# NB-IOT.net
KiCad netlist of a schematic drawn in Altium Designer
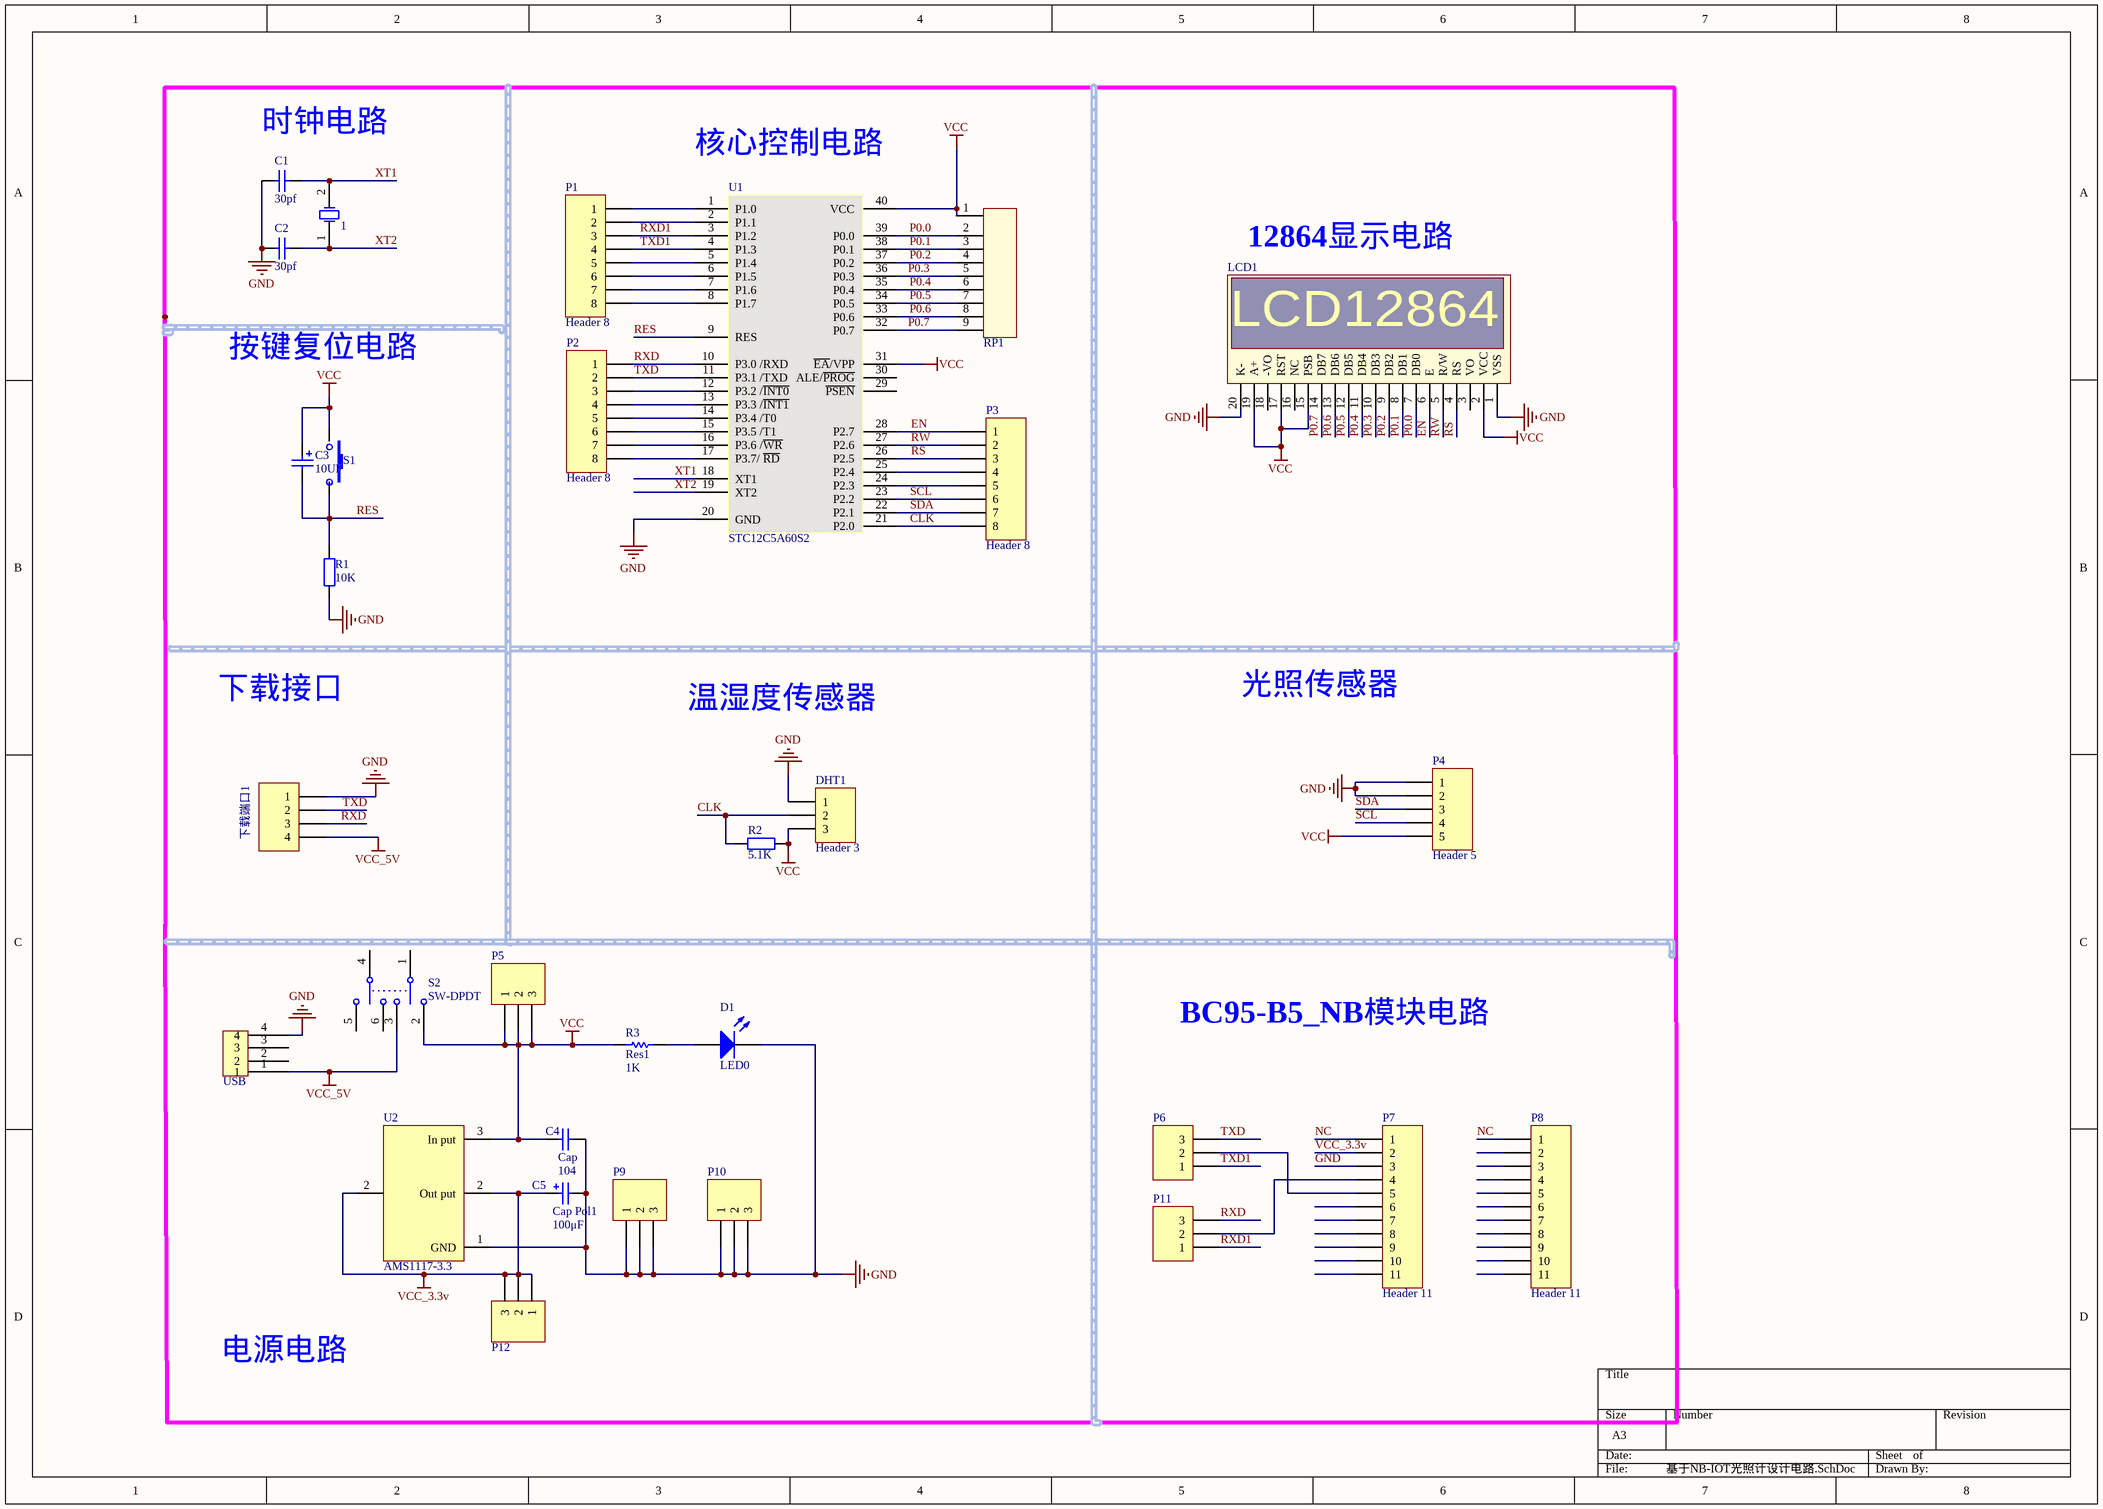
[diagram p0: 基于NB-IOT光照计设计电路.SchDoc]

(export (version "E")
  (design (tool "Eeschema 10.0.6"))
  (components
    (comp (ref "1") (value "XTAL") (footprint "4.直插晶振") (libsource (lib "小莫自创原理图库") (part "XTAL")))
    (comp (ref "C1") (value "30pf") (footprint "2.瓷片电容") (libsource (lib "小莫自创原理图库") (part "CAP")))
    (comp (ref "C2") (value "30pf") (footprint "2.瓷片电容") (libsource (lib "小莫自创原理图库") (part "CAP")))
    (comp (ref "C3") (value "10UF") (footprint "C100A") (libsource (lib "智能环境监测") (part "C-100")))
    (comp (ref "C4")
      (value "Cap")
      (footprint "CAP")
      (description "Capacitor")
      (fields (field (name "ALTIUM_VALUE") "104") (field (name "PUBLISHER") "Altium Limited"))
      (libsource (lib "Student Power Supply") (part "Cap"))
    )
    (comp (ref "C5")
      (value "Cap Pol1")
      (footprint "Cap+")
      (description "Polarized Capacitor (Radial)")
      (fields (field (name "ALTIUM_VALUE") "100μF") (field (name "PUBLISHER") "Altium Limited"))
      (libsource (lib "学生电源") (part "Cap Pol1"))
    )
    (comp (ref "D1")
      (value "LED0")
      (footprint "LED-2")
      (description "Typical INFRARED GaAs LED")
      (fields (field (name "PUBLISHER") "Altium Limited"))
      (libsource (lib "学生电源") (part "LED0"))
    )
    (comp (ref "DHT1")
      (value "Header 3")
      (footprint "HDR1X3")
      (description "Header, 3-Pin")
      (fields (field (name "PUBLISHER") "Altium Limited"))
      (libsource (lib "Miscellaneous Connectors") (part "Header 3"))
    )
    (comp (ref "LCD1") (value "~") (footprint "LCD12864") (libsource (lib "小莫自创原理图库") (part "LCD1")))
    (comp (ref "P1")
      (value "Header 8")
      (footprint "HDR1X8")
      (description "Header, 8-Pin")
      (fields (field (name "PUBLISHER") "Altium Limited"))
      (libsource (lib "Miscellaneous Connectors") (part "Header 8"))
    )
    (comp (ref "P2")
      (value "Header 8")
      (footprint "HDR1X8")
      (description "Header, 8-Pin")
      (fields (field (name "PUBLISHER") "Altium Limited"))
      (libsource (lib "Miscellaneous Connectors") (part "Header 8"))
    )
    (comp (ref "P3")
      (value "Header 8")
      (footprint "HDR1X8")
      (description "Header, 8-Pin")
      (fields (field (name "PUBLISHER") "Altium Limited"))
      (libsource (lib "") (part "Header 8_1"))
    )
    (comp (ref "P4")
      (value "Header 5")
      (footprint "HDR1X5")
      (description "Header, 5-Pin")
      (fields (field (name "PUBLISHER") "Altium Limited"))
      (libsource (lib "Miscellaneous Connectors") (part "Header 5"))
    )
    (comp (ref "P5")
      (value "~")
      (footprint "HDR1X3")
      (description "Header, 3-Pin")
      (fields (field (name "PUBLISHER") "Altium Limited"))
      (libsource (lib "学生电源") (part "Header 3"))
    )
    (comp (ref "P6")
      (value "~")
      (footprint "HDR1X3")
      (description "Header, 3-Pin")
      (fields (field (name "PUBLISHER") "Altium Limited"))
      (libsource (lib "") (part "Header 3_1"))
    )
    (comp (ref "P7")
      (value "Header 11")
      (footprint "HDR1X11")
      (description "Header, 11-Pin")
      (fields (field (name "PUBLISHER") "Altium Limited"))
      (libsource (lib "Miscellaneous Connectors") (part "Header 11"))
    )
    (comp (ref "P8")
      (value "Header 11")
      (footprint "HDR1X11")
      (description "Header, 11-Pin")
      (fields (field (name "PUBLISHER") "Altium Limited"))
      (libsource (lib "Miscellaneous Connectors") (part "Header 11"))
    )
    (comp (ref "P9")
      (value "~")
      (footprint "HDR1X3")
      (description "Header, 3-Pin")
      (fields (field (name "PUBLISHER") "Altium Limited"))
      (libsource (lib "学生电源") (part "Header 3"))
    )
    (comp (ref "P10")
      (value "~")
      (footprint "HDR1X3")
      (description "Header, 3-Pin")
      (fields (field (name "PUBLISHER") "Altium Limited"))
      (libsource (lib "学生电源") (part "Header 3"))
    )
    (comp (ref "P11")
      (value "~")
      (footprint "HDR1X3")
      (description "Header, 3-Pin")
      (fields (field (name "PUBLISHER") "Altium Limited"))
      (libsource (lib "") (part "Header 3_1"))
    )
    (comp (ref "P12")
      (value "~")
      (footprint "HDR1X3")
      (description "Header, 3-Pin")
      (fields (field (name "PUBLISHER") "Altium Limited"))
      (libsource (lib "") (part "Header 3_2"))
    )
    (comp (ref "R1") (value "10K") (footprint "R-300 1/4W") (libsource (lib "小莫自创原理图库") (part "R1")))
    (comp (ref "R2") (value "5.1K") (footprint "R-300 1/4W") (libsource (lib "") (part "R1_1")))
    (comp (ref "R3")
      (value "Res1")
      (footprint "AXIAL-0.3")
      (description "Resistor")
      (fields (field (name "ALTIUM_VALUE") "1K") (field (name "PUBLISHER") "Altium Limited"))
      (libsource (lib "学生电源") (part "Res1"))
    )
    (comp (ref "RP1") (value "RESPACK-8") (footprint "3.排阻") (libsource (lib "小莫自创原理图库") (part "RESPACK-8")))
    (comp (ref "S1")
      (value "~")
      (footprint "KEY1")
      (libsource (lib "altium-import") (part "root_3__烟雾报警.SCHLIB"))
    )
    (comp (ref "S2")
      (value "SW-DPDT")
      (footprint "swichX6")
      (description "Double-Pole, Double-Throw Switch")
      (fields (field (name "PUBLISHER") "Altium Limited"))
      (libsource (lib "Student Power Supply") (part "SW-DPDT"))
    )
    (comp (ref "U1")
      (value "STC12C5A60S2")
      (footprint "DIP-40")
      (libsource (lib "小莫自创原理图库") (part "STC89C52"))
    )
    (comp (ref "U2")
      (value "AMS1117-3.3")
      (footprint "AMS1117")
      (libsource (lib "学生电源") (part "AMS1117-3.3"))
    )
    (comp (ref "Usb1") (value "USB") (footprint "USB-A") (libsource (lib "学生电源") (part "USB")))
    (comp (ref "下载端口1")
      (value "气体")
      (footprint "HDR1X4")
      (description "Header, 4-Pin")
      (fields (field (name "PUBLISHER") "Altium Limited"))
      (libsource (lib "Miscellaneous Connectors") (part "Header 4"))
    )
  )
  (nets
    (net (code "1") (name "/CLK") (class "Default")
      (node (ref "DHT1") (pin "2") (pinfunction "2_2") (pintype "passive"))
      (node (ref "P3") (pin "8") (pinfunction "8_8") (pintype "passive"))
      (node (ref "R2") (pin "2") (pinfunction "2_2") (pintype "passive"))
      (node (ref "U1") (pin "21") (pinfunction "P2.0_21") (pintype "passive"))
    )
    (net (code "2") (name "/EN") (class "Default")
      (node (ref "LCD1") (pin "6") (pinfunction "E_6") (pintype "passive"))
      (node (ref "P3") (pin "1") (pinfunction "1_1") (pintype "passive"))
      (node (ref "U1") (pin "28") (pinfunction "P2.7_28") (pintype "passive"))
    )
    (net (code "3") (name "/NC") (class "Default")
      (node (ref "P7") (pin "1") (pinfunction "1_1") (pintype "passive"))
      (node (ref "P8") (pin "1") (pinfunction "1_1") (pintype "passive"))
    )
    (net (code "4") (name "/P0.0") (class "Default")
      (node (ref "LCD1") (pin "7") (pinfunction "DB0_7") (pintype "passive"))
      (node (ref "RP1") (pin "2") (pinfunction "2_2") (pintype "passive"))
      (node (ref "U1") (pin "39") (pinfunction "P0.0_39") (pintype "passive"))
    )
    (net (code "5") (name "/P0.1") (class "Default")
      (node (ref "LCD1") (pin "8") (pinfunction "DB1_8") (pintype "passive"))
      (node (ref "RP1") (pin "3") (pinfunction "3_3") (pintype "passive"))
      (node (ref "U1") (pin "38") (pinfunction "P0.1_38") (pintype "passive"))
    )
    (net (code "6") (name "/P0.2") (class "Default")
      (node (ref "LCD1") (pin "9") (pinfunction "DB2_9") (pintype "passive"))
      (node (ref "RP1") (pin "4") (pinfunction "4_4") (pintype "passive"))
      (node (ref "U1") (pin "37") (pinfunction "P0.2_37") (pintype "passive"))
    )
    (net (code "7") (name "/P0.3") (class "Default")
      (node (ref "LCD1") (pin "10") (pinfunction "DB3_10") (pintype "passive"))
      (node (ref "RP1") (pin "5") (pinfunction "5_5") (pintype "passive"))
      (node (ref "U1") (pin "36") (pinfunction "P0.3_36") (pintype "passive"))
    )
    (net (code "8") (name "/P0.4") (class "Default")
      (node (ref "LCD1") (pin "11") (pinfunction "DB4_11") (pintype "passive"))
      (node (ref "RP1") (pin "6") (pinfunction "6_6") (pintype "passive"))
      (node (ref "U1") (pin "35") (pinfunction "P0.4_35") (pintype "passive"))
    )
    (net (code "9") (name "/P0.5") (class "Default")
      (node (ref "LCD1") (pin "12") (pinfunction "DB5_12") (pintype "passive"))
      (node (ref "RP1") (pin "7") (pinfunction "7_7") (pintype "passive"))
      (node (ref "U1") (pin "34") (pinfunction "P0.5_34") (pintype "passive"))
    )
    (net (code "10") (name "/P0.6") (class "Default")
      (node (ref "LCD1") (pin "13") (pinfunction "DB6_13") (pintype "passive"))
      (node (ref "RP1") (pin "8") (pinfunction "8_8") (pintype "passive"))
      (node (ref "U1") (pin "33") (pinfunction "P0.6_33") (pintype "passive"))
    )
    (net (code "11") (name "/P0.7") (class "Default")
      (node (ref "LCD1") (pin "14") (pinfunction "DB7_14") (pintype "passive"))
      (node (ref "RP1") (pin "9") (pinfunction "9_9") (pintype "passive"))
      (node (ref "U1") (pin "32") (pinfunction "P0.7_32") (pintype "passive"))
    )
    (net (code "12") (name "/RES") (class "Default")
      (node (ref "C3") (pin "2") (pinfunction "2_2") (pintype "passive"))
      (node (ref "R1") (pin "1") (pinfunction "1_1") (pintype "passive"))
      (node (ref "S1") (pin "2") (pinfunction "2_2") (pintype "passive"))
      (node (ref "U1") (pin "9") (pinfunction "RES_9") (pintype "passive"))
    )
    (net (code "13") (name "/RS") (class "Default")
      (node (ref "LCD1") (pin "4") (pinfunction "RS_4") (pintype "passive"))
      (node (ref "P3") (pin "3") (pinfunction "3_3") (pintype "passive"))
      (node (ref "U1") (pin "26") (pinfunction "P2.5_26") (pintype "passive"))
    )
    (net (code "14") (name "/RW") (class "Default")
      (node (ref "LCD1") (pin "5") (pinfunction "R/W_5") (pintype "passive"))
      (node (ref "P3") (pin "2") (pinfunction "2_2") (pintype "passive"))
      (node (ref "U1") (pin "27") (pinfunction "P2.6_27") (pintype "passive"))
    )
    (net (code "15") (name "/RXD") (class "Default")
      (node (ref "P11") (pin "3") (pinfunction "3_3") (pintype "passive"))
      (node (ref "P2") (pin "1") (pinfunction "1_1") (pintype "passive"))
      (node (ref "U1") (pin "10") (pinfunction "P3.0_/RXD_10") (pintype "passive"))
      (node (ref "下载端口1") (pin "3") (pinfunction "3_3") (pintype "passive"))
    )
    (net (code "16") (name "/RXD1") (class "Default")
      (node (ref "P1") (pin "3") (pinfunction "3_3") (pintype "passive"))
      (node (ref "P11") (pin "1") (pinfunction "1_1") (pintype "passive"))
      (node (ref "U1") (pin "3") (pinfunction "P1.2_3") (pintype "passive"))
    )
    (net (code "17") (name "/SCL") (class "Default")
      (node (ref "P3") (pin "6") (pinfunction "6_6") (pintype "passive"))
      (node (ref "P4") (pin "4") (pinfunction "4_4") (pintype "passive"))
      (node (ref "U1") (pin "23") (pinfunction "P2.2_23") (pintype "passive"))
    )
    (net (code "18") (name "/SDA") (class "Default")
      (node (ref "P3") (pin "7") (pinfunction "7_7") (pintype "passive"))
      (node (ref "P4") (pin "3") (pinfunction "3_3") (pintype "passive"))
      (node (ref "U1") (pin "22") (pinfunction "P2.1_22") (pintype "passive"))
    )
    (net (code "19") (name "/TXD") (class "Default")
      (node (ref "P2") (pin "2") (pinfunction "2_2") (pintype "passive"))
      (node (ref "P6") (pin "3") (pinfunction "3_3") (pintype "passive"))
      (node (ref "U1") (pin "11") (pinfunction "P3.1_/TXD_11") (pintype "passive"))
      (node (ref "下载端口1") (pin "2") (pinfunction "2_2") (pintype "passive"))
    )
    (net (code "20") (name "/TXD1") (class "Default")
      (node (ref "P1") (pin "4") (pinfunction "4_4") (pintype "passive"))
      (node (ref "P6") (pin "1") (pinfunction "1_1") (pintype "passive"))
      (node (ref "U1") (pin "4") (pinfunction "P1.3_4") (pintype "passive"))
    )
    (net (code "21") (name "/XT1") (class "Default")
      (node (ref "1") (pin "2") (pinfunction "OSC2_2") (pintype "passive"))
      (node (ref "C1") (pin "2") (pinfunction "2_2") (pintype "passive"))
      (node (ref "U1") (pin "18") (pinfunction "XT1_18") (pintype "passive"))
    )
    (net (code "22") (name "/XT2") (class "Default")
      (node (ref "1") (pin "1") (pinfunction "OSC1_1") (pintype "passive"))
      (node (ref "C2") (pin "2") (pinfunction "2_2") (pintype "passive"))
      (node (ref "U1") (pin "19") (pinfunction "XT2_19") (pintype "passive"))
    )
    (net (code "23") (name "GND") (class "Default")
      (node (ref "C1") (pin "1") (pinfunction "1_1") (pintype "passive"))
      (node (ref "C2") (pin "1") (pinfunction "1_1") (pintype "passive"))
      (node (ref "C4") (pin "2") (pinfunction "2_2") (pintype "passive"))
      (node (ref "C5") (pin "2") (pinfunction "2_2") (pintype "passive"))
      (node (ref "D1") (pin "2") (pinfunction "K_2") (pintype "passive"))
      (node (ref "DHT1") (pin "1") (pinfunction "1_1") (pintype "passive"))
      (node (ref "LCD1") (pin "1") (pinfunction "VSS_1") (pintype "passive"))
      (node (ref "LCD1") (pin "20") (pinfunction "K-_20") (pintype "passive"))
      (node (ref "P10") (pin "1") (pinfunction "1_1") (pintype "passive"))
      (node (ref "P10") (pin "2") (pinfunction "2_2") (pintype "passive"))
      (node (ref "P10") (pin "3") (pinfunction "3_3") (pintype "passive"))
      (node (ref "P4") (pin "1") (pinfunction "1_1") (pintype "passive"))
      (node (ref "P4") (pin "2") (pinfunction "2_2") (pintype "passive"))
      (node (ref "P7") (pin "3") (pinfunction "3_3") (pintype "passive"))
      (node (ref "P9") (pin "1") (pinfunction "1_1") (pintype "passive"))
      (node (ref "P9") (pin "2") (pinfunction "2_2") (pintype "passive"))
      (node (ref "P9") (pin "3") (pinfunction "3_3") (pintype "passive"))
      (node (ref "R1") (pin "2") (pinfunction "2_2") (pintype "passive"))
      (node (ref "U1") (pin "20") (pinfunction "GND_20") (pintype "passive"))
      (node (ref "U2") (pin "1") (pinfunction "GND_1") (pintype "passive"))
      (node (ref "Usb1") (pin "4") (pinfunction "4_4") (pintype "passive"))
      (node (ref "下载端口1") (pin "1") (pinfunction "1_1") (pintype "passive"))
    )
    (net (code "24") (name "Net-(D1-A)") (class "Default")
      (node (ref "D1") (pin "1") (pinfunction "A_1") (pintype "passive"))
      (node (ref "R3") (pin "2") (pinfunction "2_2") (pintype "passive"))
    )
    (net (code "25") (name "Net-(P6-Pad2)") (class "Default")
      (node (ref "P6") (pin "2") (pinfunction "2_2") (pintype "passive"))
      (node (ref "P7") (pin "5") (pinfunction "5_5") (pintype "passive"))
    )
    (net (code "26") (name "Net-(P11-Pad2)") (class "Default")
      (node (ref "P11") (pin "2") (pinfunction "2_2") (pintype "passive"))
      (node (ref "P7") (pin "4") (pinfunction "4_4") (pintype "passive"))
    )
    (net (code "27") (name "Net-(U1-P1.0)") (class "Default")
      (node (ref "P1") (pin "1") (pinfunction "1_1") (pintype "passive"))
      (node (ref "U1") (pin "1") (pinfunction "P1.0_1") (pintype "passive"))
    )
    (net (code "28") (name "Net-(U1-P1.1)") (class "Default")
      (node (ref "P1") (pin "2") (pinfunction "2_2") (pintype "passive"))
      (node (ref "U1") (pin "2") (pinfunction "P1.1_2") (pintype "passive"))
    )
    (net (code "29") (name "Net-(U1-P1.4)") (class "Default")
      (node (ref "P1") (pin "5") (pinfunction "5_5") (pintype "passive"))
      (node (ref "U1") (pin "5") (pinfunction "P1.4_5") (pintype "passive"))
    )
    (net (code "30") (name "Net-(U1-P1.5)") (class "Default")
      (node (ref "P1") (pin "6") (pinfunction "6_6") (pintype "passive"))
      (node (ref "U1") (pin "6") (pinfunction "P1.5_6") (pintype "passive"))
    )
    (net (code "31") (name "Net-(U1-P1.6)") (class "Default")
      (node (ref "P1") (pin "7") (pinfunction "7_7") (pintype "passive"))
      (node (ref "U1") (pin "7") (pinfunction "P1.6_7") (pintype "passive"))
    )
    (net (code "32") (name "Net-(U1-P1.7)") (class "Default")
      (node (ref "P1") (pin "8") (pinfunction "8_8") (pintype "passive"))
      (node (ref "U1") (pin "8") (pinfunction "P1.7_8") (pintype "passive"))
    )
    (net (code "33") (name "Net-(U1-P2.3)") (class "Default")
      (node (ref "P3") (pin "5") (pinfunction "5_5") (pintype "passive"))
      (node (ref "U1") (pin "24") (pinfunction "P2.3_24") (pintype "passive"))
    )
    (net (code "34") (name "Net-(U1-P2.4)") (class "Default")
      (node (ref "P3") (pin "4") (pinfunction "4_4") (pintype "passive"))
      (node (ref "U1") (pin "25") (pinfunction "P2.4_25") (pintype "passive"))
    )
    (net (code "35") (name "Net-(U1-P3.2_{slash}~{INT0})") (class "Default")
      (node (ref "P2") (pin "3") (pinfunction "3_3") (pintype "passive"))
      (node (ref "U1") (pin "12") (pinfunction "P3.2_/~{INT0}_12") (pintype "passive"))
    )
    (net (code "36") (name "Net-(U1-P3.3_{slash}~{INT1})") (class "Default")
      (node (ref "P2") (pin "4") (pinfunction "4_4") (pintype "passive"))
      (node (ref "U1") (pin "13") (pinfunction "P3.3_/~{INT1}_13") (pintype "passive"))
    )
    (net (code "37") (name "Net-(U1-P3.4_{slash}T0)") (class "Default")
      (node (ref "P2") (pin "5") (pinfunction "5_5") (pintype "passive"))
      (node (ref "U1") (pin "14") (pinfunction "P3.4_/T0_14") (pintype "passive"))
    )
    (net (code "38") (name "Net-(U1-P3.5_{slash}T1)") (class "Default")
      (node (ref "P2") (pin "6") (pinfunction "6_6") (pintype "passive"))
      (node (ref "U1") (pin "15") (pinfunction "P3.5_/T1_15") (pintype "passive"))
    )
    (net (code "39") (name "Net-(U1-P3.6_{slash}~{WR})") (class "Default")
      (node (ref "P2") (pin "7") (pinfunction "7_7") (pintype "passive"))
      (node (ref "U1") (pin "16") (pinfunction "P3.6_/~{WR}_16") (pintype "passive"))
    )
    (net (code "40") (name "Net-(U1-P3.7{slash}_~{RD})") (class "Default")
      (node (ref "P2") (pin "8") (pinfunction "8_8") (pintype "passive"))
      (node (ref "U1") (pin "17") (pinfunction "P3.7/_~{RD}_17") (pintype "passive"))
    )
    (net (code "41") (name "VCC") (class "Default")
      (node (ref "C3") (pin "1") (pinfunction "1_1") (pintype "passive"))
      (node (ref "C4") (pin "1") (pinfunction "1_1") (pintype "passive"))
      (node (ref "DHT1") (pin "3") (pinfunction "3_3") (pintype "passive"))
      (node (ref "LCD1") (pin "15") (pinfunction "PSB_15") (pintype "passive"))
      (node (ref "LCD1") (pin "17") (pinfunction "RST_17") (pintype "passive"))
      (node (ref "LCD1") (pin "19") (pinfunction "A+_19") (pintype "passive"))
      (node (ref "LCD1") (pin "2") (pinfunction "VCC_2") (pintype "passive"))
      (node (ref "P4") (pin "5") (pinfunction "5_5") (pintype "passive"))
      (node (ref "P5") (pin "1") (pinfunction "1_1") (pintype "passive"))
      (node (ref "P5") (pin "2") (pinfunction "2_2") (pintype "passive"))
      (node (ref "P5") (pin "3") (pinfunction "3_3") (pintype "passive"))
      (node (ref "R2") (pin "1") (pinfunction "1_1") (pintype "passive"))
      (node (ref "R3") (pin "1") (pinfunction "1_1") (pintype "passive"))
      (node (ref "RP1") (pin "1") (pinfunction "1_1") (pintype "passive"))
      (node (ref "S1") (pin "1") (pinfunction "1_1") (pintype "passive"))
      (node (ref "S2") (pin "2") (pinfunction "2_2") (pintype "passive"))
      (node (ref "U1") (pin "31") (pinfunction "~{EA}/VPP_31") (pintype "passive"))
      (node (ref "U1") (pin "40") (pinfunction "VCC_40") (pintype "passive"))
      (node (ref "U2") (pin "3") (pinfunction "In_put_3") (pintype "passive"))
    )
    (net (code "42") (name "VCC_3.3v") (class "Default")
      (node (ref "C5") (pin "1") (pinfunction "1_1") (pintype "passive"))
      (node (ref "P12") (pin "1") (pinfunction "1_1") (pintype "passive"))
      (node (ref "P12") (pin "2") (pinfunction "2_2") (pintype "passive"))
      (node (ref "P12") (pin "3") (pinfunction "3_3") (pintype "passive"))
      (node (ref "P7") (pin "2") (pinfunction "2_2") (pintype "passive"))
      (node (ref "U2") (pin "2") (pinfunction "Out_Put_2") (pintype "passive"))
    )
    (net (code "43") (name "VCC_5V") (class "Default")
      (node (ref "S2") (pin "3") (pinfunction "3_3") (pintype "passive"))
      (node (ref "Usb1") (pin "1") (pinfunction "1_1") (pintype "passive"))
      (node (ref "下载端口1") (pin "4") (pinfunction "4_4") (pintype "passive"))
    )
    (net (code "44") (name "unconnected-(LCD1--VO-Pad18)") (class "Default")
      (node (ref "LCD1") (pin "18") (pinfunction "-VO_18") (pintype "passive"))
    )
    (net (code "45") (name "unconnected-(LCD1-NC-Pad16)") (class "Default")
      (node (ref "LCD1") (pin "16") (pinfunction "NC_16") (pintype "passive"))
    )
    (net (code "46") (name "unconnected-(LCD1-VO-Pad3)") (class "Default")
      (node (ref "LCD1") (pin "3") (pinfunction "VO_3") (pintype "passive"))
    )
    (net (code "47") (name "unconnected-(P7-Pad6)") (class "Default")
      (node (ref "P7") (pin "6") (pinfunction "6_6") (pintype "passive"))
    )
    (net (code "48") (name "unconnected-(P7-Pad7)") (class "Default")
      (node (ref "P7") (pin "7") (pinfunction "7_7") (pintype "passive"))
    )
    (net (code "49") (name "unconnected-(P7-Pad8)") (class "Default")
      (node (ref "P7") (pin "8") (pinfunction "8_8") (pintype "passive"))
    )
    (net (code "50") (name "unconnected-(P7-Pad9)") (class "Default")
      (node (ref "P7") (pin "9") (pinfunction "9_9") (pintype "passive"))
    )
    (net (code "51") (name "unconnected-(P7-Pad10)") (class "Default")
      (node (ref "P7") (pin "10") (pinfunction "10_10") (pintype "passive"))
    )
    (net (code "52") (name "unconnected-(P7-Pad11)") (class "Default")
      (node (ref "P7") (pin "11") (pinfunction "11_11") (pintype "passive"))
    )
    (net (code "53") (name "unconnected-(P8-Pad2)") (class "Default")
      (node (ref "P8") (pin "2") (pinfunction "2_2") (pintype "passive"))
    )
    (net (code "54") (name "unconnected-(P8-Pad3)") (class "Default")
      (node (ref "P8") (pin "3") (pinfunction "3_3") (pintype "passive"))
    )
    (net (code "55") (name "unconnected-(P8-Pad4)") (class "Default")
      (node (ref "P8") (pin "4") (pinfunction "4_4") (pintype "passive"))
    )
    (net (code "56") (name "unconnected-(P8-Pad5)") (class "Default")
      (node (ref "P8") (pin "5") (pinfunction "5_5") (pintype "passive"))
    )
    (net (code "57") (name "unconnected-(P8-Pad6)") (class "Default")
      (node (ref "P8") (pin "6") (pinfunction "6_6") (pintype "passive"))
    )
    (net (code "58") (name "unconnected-(P8-Pad7)") (class "Default")
      (node (ref "P8") (pin "7") (pinfunction "7_7") (pintype "passive"))
    )
    (net (code "59") (name "unconnected-(P8-Pad8)") (class "Default")
      (node (ref "P8") (pin "8") (pinfunction "8_8") (pintype "passive"))
    )
    (net (code "60") (name "unconnected-(P8-Pad9)") (class "Default")
      (node (ref "P8") (pin "9") (pinfunction "9_9") (pintype "passive"))
    )
    (net (code "61") (name "unconnected-(P8-Pad10)") (class "Default")
      (node (ref "P8") (pin "10") (pinfunction "10_10") (pintype "passive"))
    )
    (net (code "62") (name "unconnected-(P8-Pad11)") (class "Default")
      (node (ref "P8") (pin "11") (pinfunction "11_11") (pintype "passive"))
    )
    (net (code "63") (name "unconnected-(S2-5-Pad6)") (class "Default")
      (node (ref "S2") (pin "6") (pinfunction "5_6") (pintype "passive"))
    )
    (net (code "64") (name "unconnected-(S2-6-Pad5)") (class "Default")
      (node (ref "S2") (pin "5") (pinfunction "6_5") (pintype "passive"))
    )
    (net (code "65") (name "unconnected-(S2-Pad1)") (class "Default")
      (node (ref "S2") (pin "1") (pinfunction "1_1") (pintype "passive"))
    )
    (net (code "66") (name "unconnected-(S2-Pad4)") (class "Default")
      (node (ref "S2") (pin "4") (pinfunction "4_4") (pintype "passive"))
    )
    (net (code "67") (name "unconnected-(U1-ALE{slash}~{PROG}-Pad30)") (class "Default")
      (node (ref "U1") (pin "30") (pinfunction "ALE/~{PROG}_30") (pintype "passive"))
    )
    (net (code "68") (name "unconnected-(U1-~{PSEN}-Pad29)") (class "Default")
      (node (ref "U1") (pin "29") (pinfunction "~{PSEN}_29") (pintype "passive"))
    )
    (net (code "69") (name "unconnected-(Usb1-Pad2)") (class "Default")
      (node (ref "Usb1") (pin "2") (pinfunction "2_2") (pintype "passive"))
    )
    (net (code "70") (name "unconnected-(Usb1-Pad3)") (class "Default")
      (node (ref "Usb1") (pin "3") (pinfunction "3_3") (pintype "passive"))
    )
  )
)
